# beaglebone.net
KiCad netlist of a schematic drawn in Altium Designer
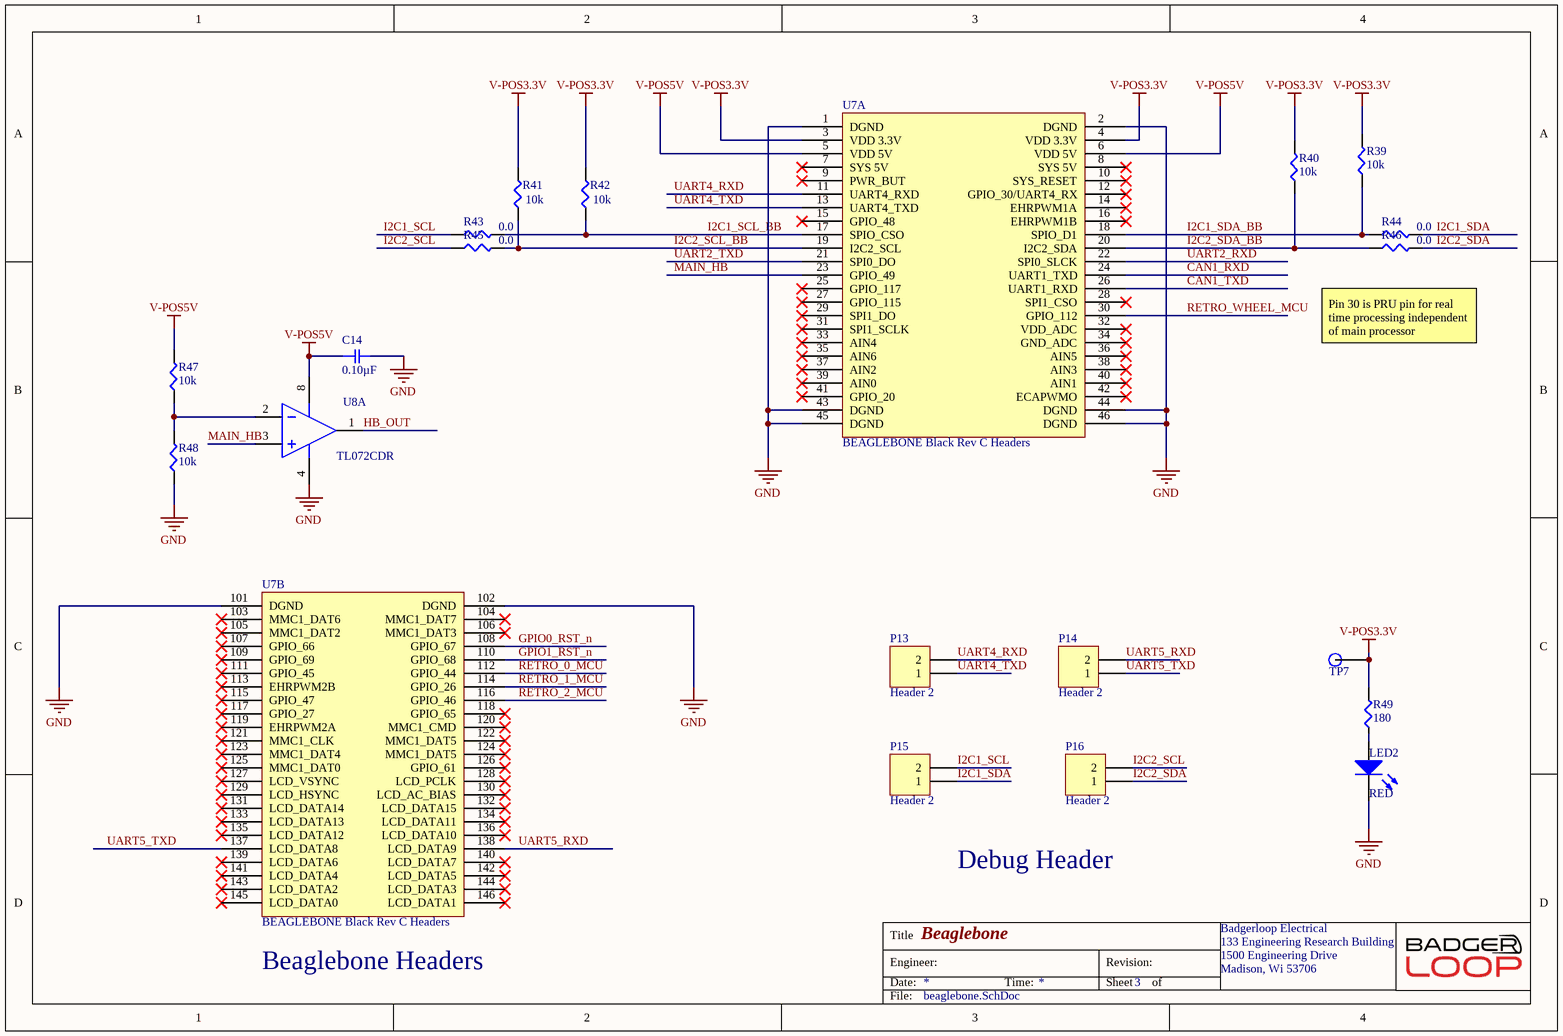
[diagram p0: beaglebone.SchDoc]

(export (version "E")
  (design (tool "Eeschema 10.0.6"))
  (components
    (comp (ref "C14")
      (value "0.10µF")
      (footprint "SMD-0805C")
      (description "CAP CER 0.1UF 10V U2J 0805")
      (fields
        (field (name "DIGI-KEY PART NUMBER") "490-11592-1-ND")
        (field (name "PART NUMBER") "GRM21B7U1A104JA01L")
      )
      (libsource (lib "capacitors") (part "GRM21B7U1A104JA01L"))
    )
    (comp (ref "LED2")
      (value "RED")
      (footprint "LED 0603 RED")
      (description "Red 631nm LED Indication - Discrete 2V 0603 (1608 Metric)")
      (fields (field (name "MANUFACTURER") "Lite-On Inc."))
      (libsource (lib "misc") (part "LED RED 0603"))
    )
    (comp (ref "P13")
      (value "Header 2")
      (footprint "Pin Header 1x2 TH Pitch 2.54mm")
      (description "Header, 2-Pin")
      (fields (field (name "PUBLISHER") "Altium Limited"))
      (libsource (lib "connector") (part "Header 2"))
    )
    (comp (ref "P14")
      (value "Header 2")
      (footprint "Pin Header 1x2 TH Pitch 2.54mm")
      (description "Header, 2-Pin")
      (fields (field (name "PUBLISHER") "Altium Limited"))
      (libsource (lib "connector") (part "Header 2"))
    )
    (comp (ref "P15")
      (value "Header 2")
      (footprint "Pin Header 1x2 TH Pitch 2.54mm")
      (description "Header, 2-Pin")
      (fields (field (name "PUBLISHER") "Altium Limited"))
      (libsource (lib "connector") (part "Header 2"))
    )
    (comp (ref "P16")
      (value "Header 2")
      (footprint "Pin Header 1x2 TH Pitch 2.54mm")
      (description "Header, 2-Pin")
      (fields (field (name "PUBLISHER") "Altium Limited"))
      (libsource (lib "connector") (part "Header 2"))
    )
    (comp (ref "R39")
      (value "10k")
      (footprint "SMD-0805-RES")
      (description "RES SMD 10K OHM 5% 1/8W 0805")
      (fields (field (name "PART NUMBER") "ERJ-6GEYJ103V") (field (name "DIGI-KEY PART NUMBER") "P10KACT-ND"))
      (libsource (lib "resistors") (part "ERJ-6GEYJ103V"))
    )
    (comp (ref "R40")
      (value "10k")
      (footprint "SMD-0805-RES")
      (description "RES SMD 10K OHM 5% 1/8W 0805")
      (fields (field (name "PART NUMBER") "ERJ-6GEYJ103V") (field (name "DIGI-KEY PART NUMBER") "P10KACT-ND"))
      (libsource (lib "resistors") (part "ERJ-6GEYJ103V"))
    )
    (comp (ref "R41")
      (value "10k")
      (footprint "SMD-0805-RES")
      (description "RES SMD 10K OHM 5% 1/8W 0805")
      (fields (field (name "PART NUMBER") "ERJ-6GEYJ103V") (field (name "DIGI-KEY PART NUMBER") "P10KACT-ND"))
      (libsource (lib "resistors") (part "ERJ-6GEYJ103V"))
    )
    (comp (ref "R42")
      (value "10k")
      (footprint "SMD-0805-RES")
      (description "RES SMD 10K OHM 5% 1/8W 0805")
      (fields (field (name "PART NUMBER") "ERJ-6GEYJ103V") (field (name "DIGI-KEY PART NUMBER") "P10KACT-ND"))
      (libsource (lib "resistors") (part "ERJ-6GEYJ103V"))
    )
    (comp (ref "R43")
      (value "0.0")
      (footprint "SMD-1206-RES")
      (description "RES SMD 0.0 OHM JUMPER 1/4W 1206")
      (fields (field (name "PART NUMBER") "ERJ-8GEY0R00V") (field (name "DIGI-KEY PART NUMBER") "P0.0ECT-ND"))
      (libsource (lib "resistors") (part "ERJ-8GEY0R00V"))
    )
    (comp (ref "R44")
      (value "0.0")
      (footprint "SMD-1206-RES")
      (description "RES SMD 0.0 OHM JUMPER 1/4W 1206")
      (fields (field (name "PART NUMBER") "ERJ-8GEY0R00V") (field (name "DIGI-KEY PART NUMBER") "P0.0ECT-ND"))
      (libsource (lib "resistors") (part "ERJ-8GEY0R00V"))
    )
    (comp (ref "R45")
      (value "0.0")
      (footprint "SMD-1206-RES")
      (description "RES SMD 0.0 OHM JUMPER 1/4W 1206")
      (fields (field (name "PART NUMBER") "ERJ-8GEY0R00V") (field (name "DIGI-KEY PART NUMBER") "P0.0ECT-ND"))
      (libsource (lib "resistors") (part "ERJ-8GEY0R00V"))
    )
    (comp (ref "R46")
      (value "0.0")
      (footprint "SMD-1206-RES")
      (description "RES SMD 0.0 OHM JUMPER 1/4W 1206")
      (fields (field (name "PART NUMBER") "ERJ-8GEY0R00V") (field (name "DIGI-KEY PART NUMBER") "P0.0ECT-ND"))
      (libsource (lib "resistors") (part "ERJ-8GEY0R00V"))
    )
    (comp (ref "R47")
      (value "10k")
      (footprint "SMD-0805-RES")
      (description "RES SMD 10K OHM 5% 1/2W 0805")
      (fields (field (name "PART NUMBER") "ERJ-P06J103V") (field (name "DIGI-KEY PART NUMBER") "P10KADCT-ND"))
      (libsource (lib "resistors") (part "ERJ-P06J103V"))
    )
    (comp (ref "R48")
      (value "10k")
      (footprint "SMD-0805-RES")
      (description "RES SMD 10K OHM 5% 1/2W 0805")
      (fields (field (name "PART NUMBER") "ERJ-P06J103V") (field (name "DIGI-KEY PART NUMBER") "P10KADCT-ND"))
      (libsource (lib "resistors") (part "ERJ-P06J103V"))
    )
    (comp (ref "R49")
      (value "180")
      (footprint "SMD-0805-RES")
      (description "RES SMD 180 OHM 1% 1/8W 0805")
      (fields (field (name "PART NUMBER") "ERJ-6ENF1800V") (field (name "DIGI-KEY PART NUMBER") "P180CCT-ND"))
      (libsource (lib "resistors") (part "ERJ-6ENF1800V"))
    )
    (comp (ref "TP7")
      (value "TP")
      (footprint "Test Point")
      (description "SMD TEST POINT")
      (libsource (lib "misc") (part "TP"))
    )
    (comp (ref "U7")
      (value "BEAGLEBONE Black Rev C Headers")
      (footprint "Beaglebone_Topside")
      (description "KIT DEV BEAGLEBONE BLACK REV C. Header Breakout")
      (libsource (lib "misc") (part "Beaglebone"))
    )
    (comp (ref "U8")
      (value "TL072CDR")
      (footprint "SOP127P600X175-8N")
      (description "IC OPAMP JFET 3MHZ 8SOIC")
      (fields (field (name "MANUFACTURER") "Texas Instruments"))
      (libsource (lib "ic") (part "TL072CDR"))
    )
  )
  (nets
    (net (code "1") (name "/CAN1_RXD") (class "Default")
      (node (ref "U7") (pin "24") (pinfunction "UART1_TXD_24") (pintype "passive"))
    )
    (net (code "2") (name "/CAN1_TXD") (class "Default")
      (node (ref "U7") (pin "26") (pinfunction "UART1_RXD_26") (pintype "passive"))
    )
    (net (code "3") (name "/GPIO0_RST_n") (class "Default")
      (node (ref "U7") (pin "108") (pinfunction "GPIO_67_108") (pintype "passive"))
    )
    (net (code "4") (name "/GPIO1_RST_n") (class "Default")
      (node (ref "U7") (pin "110") (pinfunction "GPIO_68_110") (pintype "passive"))
    )
    (net (code "5") (name "/HB_OUT") (class "Default")
      (node (ref "U8") (pin "1") (pinfunction "OUT_1") (pintype "passive"))
    )
    (net (code "6") (name "/I2C1_SCL") (class "Default")
      (node (ref "P15") (pin "2") (pinfunction "2_2") (pintype "passive"))
      (node (ref "R43") (pin "1") (pinfunction "1_1") (pintype "passive"))
    )
    (net (code "7") (name "/I2C1_SCL_BB") (class "Default")
      (node (ref "R42") (pin "1") (pinfunction "1_1") (pintype "passive"))
      (node (ref "R43") (pin "2") (pinfunction "2_2") (pintype "passive"))
      (node (ref "U7") (pin "17") (pinfunction "SPIO_CSO_17") (pintype "passive"))
    )
    (net (code "8") (name "/I2C1_SDA") (class "Default")
      (node (ref "P15") (pin "1") (pinfunction "1_1") (pintype "passive"))
      (node (ref "R44") (pin "2") (pinfunction "2_2") (pintype "passive"))
    )
    (net (code "9") (name "/I2C1_SDA_BB") (class "Default")
      (node (ref "R39") (pin "1") (pinfunction "1_1") (pintype "passive"))
      (node (ref "R44") (pin "1") (pinfunction "1_1") (pintype "passive"))
      (node (ref "U7") (pin "18") (pinfunction "SPIO_D1_18") (pintype "passive"))
    )
    (net (code "10") (name "/I2C2_SCL") (class "Default")
      (node (ref "P16") (pin "2") (pinfunction "2_2") (pintype "passive"))
      (node (ref "R45") (pin "1") (pinfunction "1_1") (pintype "passive"))
    )
    (net (code "11") (name "/I2C2_SCL_BB") (class "Default")
      (node (ref "R41") (pin "1") (pinfunction "1_1") (pintype "passive"))
      (node (ref "R45") (pin "2") (pinfunction "2_2") (pintype "passive"))
      (node (ref "U7") (pin "19") (pinfunction "I2C2_SCL_19") (pintype "passive"))
    )
    (net (code "12") (name "/I2C2_SDA") (class "Default")
      (node (ref "P16") (pin "1") (pinfunction "1_1") (pintype "passive"))
      (node (ref "R46") (pin "2") (pinfunction "2_2") (pintype "passive"))
    )
    (net (code "13") (name "/I2C2_SDA_BB") (class "Default")
      (node (ref "R40") (pin "1") (pinfunction "1_1") (pintype "passive"))
      (node (ref "R46") (pin "1") (pinfunction "1_1") (pintype "passive"))
      (node (ref "U7") (pin "20") (pinfunction "I2C2_SDA_20") (pintype "passive"))
    )
    (net (code "14") (name "/MAIN_HB") (class "Default")
      (node (ref "U7") (pin "23") (pinfunction "GPIO_49_23") (pintype "passive"))
      (node (ref "U8") (pin "3") (pinfunction "IN+_3") (pintype "passive"))
    )
    (net (code "15") (name "/RETRO_0_MCU") (class "Default")
      (node (ref "U7") (pin "112") (pinfunction "GPIO_44_112") (pintype "passive"))
    )
    (net (code "16") (name "/RETRO_1_MCU") (class "Default")
      (node (ref "U7") (pin "114") (pinfunction "GPIO_26_114") (pintype "passive"))
    )
    (net (code "17") (name "/RETRO_2_MCU") (class "Default")
      (node (ref "U7") (pin "116") (pinfunction "GPIO_46_116") (pintype "passive"))
    )
    (net (code "18") (name "/RETRO_WHEEL_MCU") (class "Default")
      (node (ref "U7") (pin "30") (pinfunction "GPIO_112_30") (pintype "passive"))
    )
    (net (code "19") (name "/UART2_RXD") (class "Default")
      (node (ref "U7") (pin "22") (pinfunction "SPI0_SLCK_22") (pintype "passive"))
    )
    (net (code "20") (name "/UART2_TXD") (class "Default")
      (node (ref "U7") (pin "21") (pinfunction "SPI0_DO_21") (pintype "passive"))
    )
    (net (code "21") (name "/UART4_RXD") (class "Default")
      (node (ref "P13") (pin "2") (pinfunction "2_2") (pintype "passive"))
      (node (ref "U7") (pin "11") (pinfunction "UART4_RXD_11") (pintype "passive"))
    )
    (net (code "22") (name "/UART4_TXD") (class "Default")
      (node (ref "P13") (pin "1") (pinfunction "1_1") (pintype "passive"))
      (node (ref "U7") (pin "13") (pinfunction "UART4_TXD_13") (pintype "passive"))
    )
    (net (code "23") (name "/UART5_RXD") (class "Default")
      (node (ref "P14") (pin "2") (pinfunction "2_2") (pintype "passive"))
      (node (ref "U7") (pin "138") (pinfunction "LCD_DATA9_138") (pintype "passive"))
    )
    (net (code "24") (name "/UART5_TXD") (class "Default")
      (node (ref "P14") (pin "1") (pinfunction "1_1") (pintype "passive"))
      (node (ref "U7") (pin "137") (pinfunction "LCD_DATA8_137") (pintype "passive"))
    )
    (net (code "25") (name "GND") (class "Default")
      (node (ref "C14") (pin "2") (pinfunction "2_2") (pintype "passive"))
      (node (ref "LED2") (pin "2") (pinfunction "K_2") (pintype "passive"))
      (node (ref "R48") (pin "1") (pinfunction "1_1") (pintype "passive"))
      (node (ref "U7") (pin "1") (pinfunction "DGND_1") (pintype "passive"))
      (node (ref "U7") (pin "101") (pinfunction "DGND_101") (pintype "passive"))
      (node (ref "U7") (pin "102") (pinfunction "DGND_102") (pintype "passive"))
      (node (ref "U7") (pin "2") (pinfunction "DGND_2") (pintype "passive"))
      (node (ref "U7") (pin "43") (pinfunction "DGND_43") (pintype "passive"))
      (node (ref "U7") (pin "44") (pinfunction "DGND_44") (pintype "passive"))
      (node (ref "U7") (pin "45") (pinfunction "DGND_45") (pintype "passive"))
      (node (ref "U7") (pin "46") (pinfunction "DGND_46") (pintype "passive"))
      (node (ref "U8") (pin "4") (pinfunction "V-_4") (pintype "power_in"))
    )
    (net (code "26") (name "Net-(LED2-A)") (class "Default")
      (node (ref "LED2") (pin "1") (pinfunction "A_1") (pintype "passive"))
      (node (ref "R49") (pin "1") (pinfunction "1_1") (pintype "passive"))
    )
    (net (code "27") (name "Net-(U8A-IN-)") (class "Default")
      (node (ref "R47") (pin "1") (pinfunction "1_1") (pintype "passive"))
      (node (ref "R48") (pin "2") (pinfunction "2_2") (pintype "passive"))
      (node (ref "U8") (pin "2") (pinfunction "IN-_2") (pintype "passive"))
    )
    (net (code "28") (name "V-POS3.3V") (class "Default")
      (node (ref "R39") (pin "2") (pinfunction "2_2") (pintype "passive"))
      (node (ref "R40") (pin "2") (pinfunction "2_2") (pintype "passive"))
      (node (ref "R41") (pin "2") (pinfunction "2_2") (pintype "passive"))
      (node (ref "R42") (pin "2") (pinfunction "2_2") (pintype "passive"))
      (node (ref "R49") (pin "2") (pinfunction "2_2") (pintype "passive"))
      (node (ref "TP7") (pin "1") (pinfunction "1_1") (pintype "passive"))
      (node (ref "U7") (pin "3") (pinfunction "VDD_3.3V_3") (pintype "passive"))
      (node (ref "U7") (pin "4") (pinfunction "VDD_3.3V_4") (pintype "passive"))
    )
    (net (code "29") (name "V-POS5V") (class "Default")
      (node (ref "C14") (pin "1") (pinfunction "1_1") (pintype "passive"))
      (node (ref "R47") (pin "2") (pinfunction "2_2") (pintype "passive"))
      (node (ref "U7") (pin "5") (pinfunction "VDD_5V_5") (pintype "passive"))
      (node (ref "U7") (pin "6") (pinfunction "VDD_5V_6") (pintype "passive"))
      (node (ref "U8") (pin "8") (pinfunction "V+_8") (pintype "power_in"))
    )
    (net (code "30") (name "unconnected-(U7A-AIN0-Pad39)") (class "Default")
      (node (ref "U7") (pin "39") (pinfunction "AIN0_39") (pintype "passive+no_connect"))
    )
    (net (code "31") (name "unconnected-(U7A-AIN1-Pad40)") (class "Default")
      (node (ref "U7") (pin "40") (pinfunction "AIN1_40") (pintype "passive+no_connect"))
    )
    (net (code "32") (name "unconnected-(U7A-AIN2-Pad37)") (class "Default")
      (node (ref "U7") (pin "37") (pinfunction "AIN2_37") (pintype "passive+no_connect"))
    )
    (net (code "33") (name "unconnected-(U7A-AIN3-Pad38)") (class "Default")
      (node (ref "U7") (pin "38") (pinfunction "AIN3_38") (pintype "passive+no_connect"))
    )
    (net (code "34") (name "unconnected-(U7A-AIN4-Pad33)") (class "Default")
      (node (ref "U7") (pin "33") (pinfunction "AIN4_33") (pintype "passive+no_connect"))
    )
    (net (code "35") (name "unconnected-(U7A-AIN5-Pad36)") (class "Default")
      (node (ref "U7") (pin "36") (pinfunction "AIN5_36") (pintype "passive+no_connect"))
    )
    (net (code "36") (name "unconnected-(U7A-AIN6-Pad35)") (class "Default")
      (node (ref "U7") (pin "35") (pinfunction "AIN6_35") (pintype "passive+no_connect"))
    )
    (net (code "37") (name "unconnected-(U7A-ECAPWMO-Pad42)") (class "Default")
      (node (ref "U7") (pin "42") (pinfunction "ECAPWMO_42") (pintype "passive+no_connect"))
    )
    (net (code "38") (name "unconnected-(U7A-EHRPWM1A-Pad14)") (class "Default")
      (node (ref "U7") (pin "14") (pinfunction "EHRPWM1A_14") (pintype "passive+no_connect"))
    )
    (net (code "39") (name "unconnected-(U7A-EHRPWM1B-Pad16)") (class "Default")
      (node (ref "U7") (pin "16") (pinfunction "EHRPWM1B_16") (pintype "passive+no_connect"))
    )
    (net (code "40") (name "unconnected-(U7A-GND_ADC-Pad34)") (class "Default")
      (node (ref "U7") (pin "34") (pinfunction "GND_ADC_34") (pintype "passive+no_connect"))
    )
    (net (code "41") (name "unconnected-(U7A-GPIO_20-Pad41)") (class "Default")
      (node (ref "U7") (pin "41") (pinfunction "GPIO_20_41") (pintype "passive+no_connect"))
    )
    (net (code "42") (name "unconnected-(U7A-GPIO_30{slash}UART4_RX-Pad12)") (class "Default")
      (node (ref "U7") (pin "12") (pinfunction "GPIO_30/UART4_RX_12") (pintype "passive+no_connect"))
    )
    (net (code "43") (name "unconnected-(U7A-GPIO_48-Pad15)") (class "Default")
      (node (ref "U7") (pin "15") (pinfunction "GPIO_48_15") (pintype "passive+no_connect"))
    )
    (net (code "44") (name "unconnected-(U7A-GPIO_115-Pad27)") (class "Default")
      (node (ref "U7") (pin "27") (pinfunction "GPIO_115_27") (pintype "passive+no_connect"))
    )
    (net (code "45") (name "unconnected-(U7A-GPIO_117-Pad25)") (class "Default")
      (node (ref "U7") (pin "25") (pinfunction "GPIO_117_25") (pintype "passive+no_connect"))
    )
    (net (code "46") (name "unconnected-(U7A-PWR_BUT-Pad9)") (class "Default")
      (node (ref "U7") (pin "9") (pinfunction "PWR_BUT_9") (pintype "passive+no_connect"))
    )
    (net (code "47") (name "unconnected-(U7A-SPI1_CSO-Pad28)") (class "Default")
      (node (ref "U7") (pin "28") (pinfunction "SPI1_CSO_28") (pintype "passive+no_connect"))
    )
    (net (code "48") (name "unconnected-(U7A-SPI1_DO-Pad29)") (class "Default")
      (node (ref "U7") (pin "29") (pinfunction "SPI1_DO_29") (pintype "passive+no_connect"))
    )
    (net (code "49") (name "unconnected-(U7A-SPI1_SCLK-Pad31)") (class "Default")
      (node (ref "U7") (pin "31") (pinfunction "SPI1_SCLK_31") (pintype "passive+no_connect"))
    )
    (net (code "50") (name "unconnected-(U7A-SYS_5V-Pad7)") (class "Default")
      (node (ref "U7") (pin "7") (pinfunction "SYS_5V_7") (pintype "passive+no_connect"))
    )
    (net (code "51") (name "unconnected-(U7A-SYS_5V-Pad8)") (class "Default")
      (node (ref "U7") (pin "8") (pinfunction "SYS_5V_8") (pintype "passive+no_connect"))
    )
    (net (code "52") (name "unconnected-(U7A-SYS_RESET-Pad10)") (class "Default")
      (node (ref "U7") (pin "10") (pinfunction "SYS_RESET_10") (pintype "passive+no_connect"))
    )
    (net (code "53") (name "unconnected-(U7A-VDD_ADC-Pad32)") (class "Default")
      (node (ref "U7") (pin "32") (pinfunction "VDD_ADC_32") (pintype "passive+no_connect"))
    )
    (net (code "54") (name "unconnected-(U7B-EHRPWM2A-Pad119)") (class "Default")
      (node (ref "U7") (pin "119") (pinfunction "EHRPWM2A_119") (pintype "passive+no_connect"))
    )
    (net (code "55") (name "unconnected-(U7B-EHRPWM2B-Pad113)") (class "Default")
      (node (ref "U7") (pin "113") (pinfunction "EHRPWM2B_113") (pintype "passive+no_connect"))
    )
    (net (code "56") (name "unconnected-(U7B-GPIO_27-Pad117)") (class "Default")
      (node (ref "U7") (pin "117") (pinfunction "GPIO_27_117") (pintype "passive+no_connect"))
    )
    (net (code "57") (name "unconnected-(U7B-GPIO_45-Pad111)") (class "Default")
      (node (ref "U7") (pin "111") (pinfunction "GPIO_45_111") (pintype "passive+no_connect"))
    )
    (net (code "58") (name "unconnected-(U7B-GPIO_47-Pad115)") (class "Default")
      (node (ref "U7") (pin "115") (pinfunction "GPIO_47_115") (pintype "passive+no_connect"))
    )
    (net (code "59") (name "unconnected-(U7B-GPIO_61-Pad126)") (class "Default")
      (node (ref "U7") (pin "126") (pinfunction "GPIO_61_126") (pintype "passive+no_connect"))
    )
    (net (code "60") (name "unconnected-(U7B-GPIO_65-Pad118)") (class "Default")
      (node (ref "U7") (pin "118") (pinfunction "GPIO_65_118") (pintype "passive+no_connect"))
    )
    (net (code "61") (name "unconnected-(U7B-GPIO_66-Pad107)") (class "Default")
      (node (ref "U7") (pin "107") (pinfunction "GPIO_66_107") (pintype "passive+no_connect"))
    )
    (net (code "62") (name "unconnected-(U7B-GPIO_69-Pad109)") (class "Default")
      (node (ref "U7") (pin "109") (pinfunction "GPIO_69_109") (pintype "passive+no_connect"))
    )
    (net (code "63") (name "unconnected-(U7B-LCD_AC_BIAS-Pad130)") (class "Default")
      (node (ref "U7") (pin "130") (pinfunction "LCD_AC_BIAS_130") (pintype "passive+no_connect"))
    )
    (net (code "64") (name "unconnected-(U7B-LCD_DATA0-Pad145)") (class "Default")
      (node (ref "U7") (pin "145") (pinfunction "LCD_DATA0_145") (pintype "passive+no_connect"))
    )
    (net (code "65") (name "unconnected-(U7B-LCD_DATA1-Pad146)") (class "Default")
      (node (ref "U7") (pin "146") (pinfunction "LCD_DATA1_146") (pintype "passive+no_connect"))
    )
    (net (code "66") (name "unconnected-(U7B-LCD_DATA2-Pad143)") (class "Default")
      (node (ref "U7") (pin "143") (pinfunction "LCD_DATA2_143") (pintype "passive+no_connect"))
    )
    (net (code "67") (name "unconnected-(U7B-LCD_DATA3-Pad144)") (class "Default")
      (node (ref "U7") (pin "144") (pinfunction "LCD_DATA3_144") (pintype "passive+no_connect"))
    )
    (net (code "68") (name "unconnected-(U7B-LCD_DATA4-Pad141)") (class "Default")
      (node (ref "U7") (pin "141") (pinfunction "LCD_DATA4_141") (pintype "passive+no_connect"))
    )
    (net (code "69") (name "unconnected-(U7B-LCD_DATA5-Pad142)") (class "Default")
      (node (ref "U7") (pin "142") (pinfunction "LCD_DATA5_142") (pintype "passive+no_connect"))
    )
    (net (code "70") (name "unconnected-(U7B-LCD_DATA6-Pad139)") (class "Default")
      (node (ref "U7") (pin "139") (pinfunction "LCD_DATA6_139") (pintype "passive+no_connect"))
    )
    (net (code "71") (name "unconnected-(U7B-LCD_DATA7-Pad140)") (class "Default")
      (node (ref "U7") (pin "140") (pinfunction "LCD_DATA7_140") (pintype "passive+no_connect"))
    )
    (net (code "72") (name "unconnected-(U7B-LCD_DATA10-Pad136)") (class "Default")
      (node (ref "U7") (pin "136") (pinfunction "LCD_DATA10_136") (pintype "passive+no_connect"))
    )
    (net (code "73") (name "unconnected-(U7B-LCD_DATA11-Pad134)") (class "Default")
      (node (ref "U7") (pin "134") (pinfunction "LCD_DATA11_134") (pintype "passive+no_connect"))
    )
    (net (code "74") (name "unconnected-(U7B-LCD_DATA12-Pad135)") (class "Default")
      (node (ref "U7") (pin "135") (pinfunction "LCD_DATA12_135") (pintype "passive+no_connect"))
    )
    (net (code "75") (name "unconnected-(U7B-LCD_DATA13-Pad133)") (class "Default")
      (node (ref "U7") (pin "133") (pinfunction "LCD_DATA13_133") (pintype "passive+no_connect"))
    )
    (net (code "76") (name "unconnected-(U7B-LCD_DATA14-Pad131)") (class "Default")
      (node (ref "U7") (pin "131") (pinfunction "LCD_DATA14_131") (pintype "passive+no_connect"))
    )
    (net (code "77") (name "unconnected-(U7B-LCD_DATA15-Pad132)") (class "Default")
      (node (ref "U7") (pin "132") (pinfunction "LCD_DATA15_132") (pintype "passive+no_connect"))
    )
    (net (code "78") (name "unconnected-(U7B-LCD_HSYNC-Pad129)") (class "Default")
      (node (ref "U7") (pin "129") (pinfunction "LCD_HSYNC_129") (pintype "passive+no_connect"))
    )
    (net (code "79") (name "unconnected-(U7B-LCD_PCLK-Pad128)") (class "Default")
      (node (ref "U7") (pin "128") (pinfunction "LCD_PCLK_128") (pintype "passive+no_connect"))
    )
    (net (code "80") (name "unconnected-(U7B-LCD_VSYNC-Pad127)") (class "Default")
      (node (ref "U7") (pin "127") (pinfunction "LCD_VSYNC_127") (pintype "passive+no_connect"))
    )
    (net (code "81") (name "unconnected-(U7B-MMC1_CLK-Pad121)") (class "Default")
      (node (ref "U7") (pin "121") (pinfunction "MMC1_CLK_121") (pintype "passive+no_connect"))
    )
    (net (code "82") (name "unconnected-(U7B-MMC1_CMD-Pad120)") (class "Default")
      (node (ref "U7") (pin "120") (pinfunction "MMC1_CMD_120") (pintype "passive+no_connect"))
    )
    (net (code "83") (name "unconnected-(U7B-MMC1_DAT0-Pad125)") (class "Default")
      (node (ref "U7") (pin "125") (pinfunction "MMC1_DAT0_125") (pintype "passive+no_connect"))
    )
    (net (code "84") (name "unconnected-(U7B-MMC1_DAT2-Pad105)") (class "Default")
      (node (ref "U7") (pin "105") (pinfunction "MMC1_DAT2_105") (pintype "passive+no_connect"))
    )
    (net (code "85") (name "unconnected-(U7B-MMC1_DAT3-Pad106)") (class "Default")
      (node (ref "U7") (pin "106") (pinfunction "MMC1_DAT3_106") (pintype "passive+no_connect"))
    )
    (net (code "86") (name "unconnected-(U7B-MMC1_DAT4-Pad123)") (class "Default")
      (node (ref "U7") (pin "123") (pinfunction "MMC1_DAT4_123") (pintype "passive+no_connect"))
    )
    (net (code "87") (name "unconnected-(U7B-MMC1_DAT5-Pad122)") (class "Default")
      (node (ref "U7") (pin "122") (pinfunction "MMC1_DAT5_122") (pintype "passive+no_connect"))
    )
    (net (code "88") (name "unconnected-(U7B-MMC1_DAT5-Pad124)") (class "Default")
      (node (ref "U7") (pin "124") (pinfunction "MMC1_DAT5_124") (pintype "passive+no_connect"))
    )
    (net (code "89") (name "unconnected-(U7B-MMC1_DAT6-Pad103)") (class "Default")
      (node (ref "U7") (pin "103") (pinfunction "MMC1_DAT6_103") (pintype "passive+no_connect"))
    )
    (net (code "90") (name "unconnected-(U7B-MMC1_DAT7-Pad104)") (class "Default")
      (node (ref "U7") (pin "104") (pinfunction "MMC1_DAT7_104") (pintype "passive+no_connect"))
    )
  )
)
